# SL1_Xilinx_Spartan-IIE_PQ208_Rev1_01.net
KiCad netlist of a schematic drawn in Altium Designer
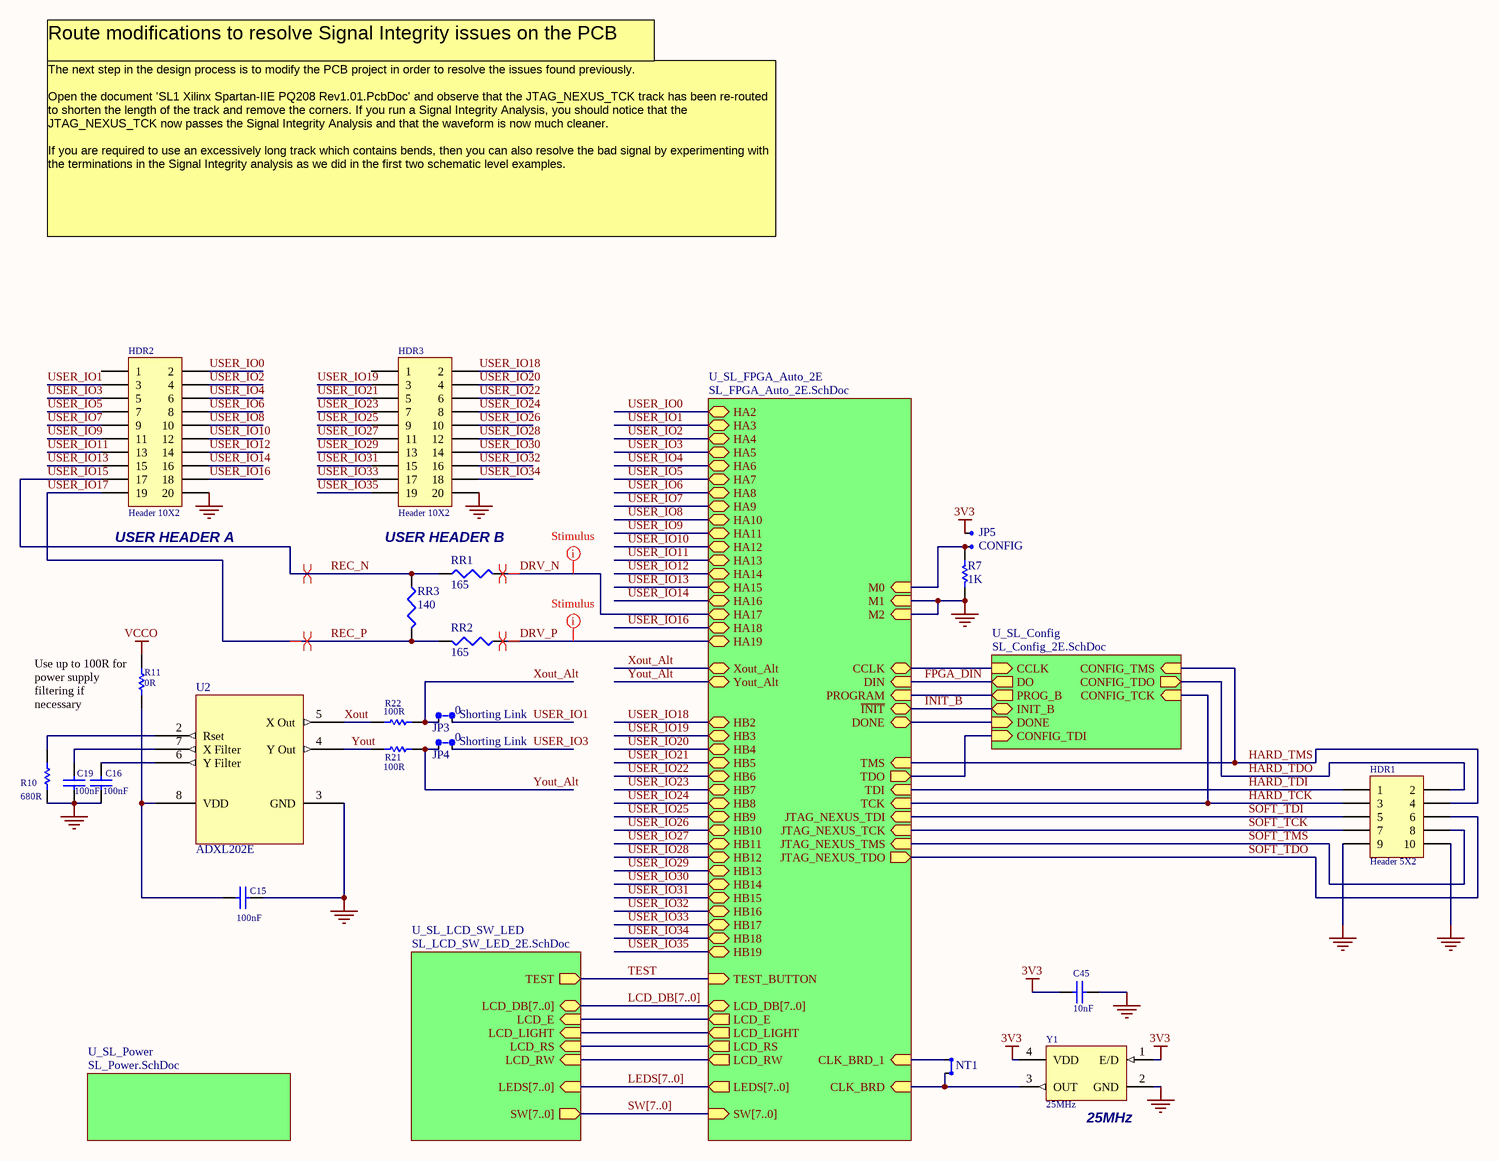
[diagram p0: SL1 Xilinx Spartan-IIE PQ208 Rev1.01.SchDoc]

(export (version "E")
  (design (tool "Eeschema 10.0.6"))
  (components
    (comp (ref "C15")
      (value "100nF")
      (footprint "CC1608-0603")
      (description "Capacitor")
      (libsource (lib "Test1") (part "CAP"))
    )
    (comp (ref "C16")
      (value "100nF")
      (footprint "CC1608-0603")
      (description "Capacitor")
      (libsource (lib "Test1") (part "CAP"))
    )
    (comp (ref "C19")
      (value "100nF")
      (footprint "CC1608-0603")
      (description "Capacitor")
      (libsource (lib "Test1") (part "CAP"))
    )
    (comp (ref "C45")
      (value "10nF")
      (footprint "CC1608-0603")
      (description "Capacitor")
      (libsource (lib "Test1") (part "CAP"))
    )
    (comp (ref "HDR1")
      (value "Header 5X2")
      (footprint "HDR2X5_LP")
      (description "Header, 5-Pin, Dual row")
      (libsource (lib "Miscellaneous Connectors") (part "Header 5X2"))
    )
    (comp (ref "HDR2")
      (value "Header 10X2")
      (footprint "Altium Nanoboard Project:HDR2X10")
      (description "Header, 10-Pin, Dual row")
      (libsource (lib "Altium Nanoboard Project") (part "Header 10X2"))
    )
    (comp (ref "HDR3")
      (value "Header 10X2")
      (footprint "Altium Nanoboard Project:HDR2X10")
      (description "Header, 10-Pin, Dual row")
      (libsource (lib "Altium Nanoboard Project") (part "Header 10X2"))
    )
    (comp (ref "JP3")
      (value "X axis")
      (footprint "Altium Nanoboard Project:HDR1X2")
      (description "Jumper, 2-Pin")
      (libsource (lib "SpiritLevel_2E") (part "Jumper, 2-Pin"))
    )
    (comp (ref "JP4")
      (value "Y axis")
      (footprint "Altium Nanoboard Project:HDR1X2")
      (description "Jumper, 2-Pin")
      (libsource (lib "SpiritLevel_2E") (part "Jumper, 2-Pin"))
    )
    (comp (ref "JP5")
      (value "CONFIG")
      (footprint "Altium Nanoboard Project:HDR1X2")
      (description "Jumper, 2-Pin")
      (libsource (lib "SpiritLevel_2E") (part "Jumper, 2-Pin"))
    )
    (comp (ref "JS2")
      (value "Shorting Link")
      (description "Shorting Link, 2.54mm (0.1\") Pitch")
      (fields (field (name "ALTIUM_VALUE") "0"))
      (libsource (lib "SpiritLevel_2E") (part "Jumper Socket"))
    )
    (comp (ref "JS3")
      (value "Shorting Link")
      (description "Shorting Link, 2.54mm (0.1\") Pitch")
      (fields (field (name "ALTIUM_VALUE") "0"))
      (libsource (lib "SpiritLevel_2E") (part "Jumper Socket"))
    )
    (comp (ref "NT1")
      (value "*")
      (footprint "NT")
      (description "Jumper, 2-Pin")
      (libsource (lib "SpiritLevel_2E") (part "Jumper, 2-Pin"))
    )
    (comp (ref "R7")
      (value "1K")
      (footprint "CR2012-0805")
      (description "Resistor")
      (libsource (lib "Altium Nanoboard Project") (part "RES"))
    )
    (comp (ref "R10")
      (value "680R")
      (footprint "CR2012-0805")
      (description "Resistor")
      (libsource (lib "Miscellaneous Devices") (part "Res1"))
    )
    (comp (ref "R11")
      (value "0R")
      (footprint "CR2012-0805")
      (description "Resistor")
      (libsource (lib "PassiveSMD") (part "RES"))
    )
    (comp (ref "R21")
      (value "100R")
      (footprint "CR2012-0805")
      (description "Resistor")
      (libsource (lib "Miscellaneous Devices") (part "Res1"))
    )
    (comp (ref "R22")
      (value "100R")
      (footprint "CR2012-0805")
      (description "Resistor")
      (libsource (lib "Miscellaneous Devices") (part "Res1"))
    )
    (comp (ref "RR1")
      (value "165")
      (footprint "J1-0603")
      (description "Resistor")
      (fields (field (name "Comment") "Res3") (field (name "PUBLISHER") "Altium Limited"))
      (libsource (lib "Miscellaneous Devices") (part "Res3"))
    )
    (comp (ref "RR2")
      (value "165")
      (footprint "J1-0603")
      (description "Resistor")
      (fields (field (name "Comment") "Res3") (field (name "PUBLISHER") "Altium Limited"))
      (libsource (lib "Miscellaneous Devices") (part "Res3"))
    )
    (comp (ref "RR3")
      (value "140")
      (footprint "J1-0603")
      (description "Resistor")
      (fields (field (name "Comment") "Res3") (field (name "PUBLISHER") "Altium Limited"))
      (libsource (lib "Miscellaneous Devices") (part "Res3"))
    )
    (comp (ref "U2")
      (value "ADXL202E")
      (footprint "Spirit_Level_Project:E-8")
      (description "Accelerometer with Digital Output")
      (libsource (lib "SpiritLevel_2E") (part "ADXL202E"))
    )
    (comp (ref "Y1")
      (value "25MHz")
      (footprint "Altium Nanoboard Project:QSMO_4200")
      (description "Surface Mount Crystal Oscillator")
      (libsource (lib "Altium Nanoboard Project") (part "QSMO_4200"))
    )
  )
  (nets
    (net (code "26") (name "/CLK_BRD") (class "Default")
      (node (ref "NT1") (pin "2") (pinfunction "2_2") (pintype "passive"))
      (node (ref "Y1") (pin "3") (pinfunction "OUT_3") (pintype "output"))
    )
    (net (code "27") (name "/CLK_BRD_1") (class "Default")
      (node (ref "NT1") (pin "1") (pinfunction "1_1") (pintype "passive"))
    )
    (net (code "29") (name "/DRV_N") (class "Default")
      (node (ref "RR1") (pin "1") (pinfunction "1_1") (pintype "passive"))
    )
    (net (code "30") (name "/DRV_P") (class "Default")
      (node (ref "RR2") (pin "2") (pinfunction "2_2") (pintype "passive"))
    )
    (net (code "32") (name "/HARD_TCK") (class "Default")
      (node (ref "HDR1") (pin "3") (pinfunction "3_3") (pintype "passive"))
    )
    (net (code "33") (name "/HARD_TDI") (class "Default")
      (node (ref "HDR1") (pin "1") (pinfunction "1_1") (pintype "passive"))
    )
    (net (code "34") (name "/HARD_TDO") (class "Default")
      (node (ref "HDR1") (pin "2") (pinfunction "2_2") (pintype "passive"))
    )
    (net (code "35") (name "/HARD_TMS") (class "Default")
      (node (ref "HDR1") (pin "4") (pinfunction "4_4") (pintype "passive"))
    )
    (net (code "43") (name "/M0") (class "Default")
      (node (ref "JP5") (pin "1") (pinfunction "1_1") (pintype "passive"))
      (node (ref "R7") (pin "2") (pinfunction "2_2") (pintype "passive"))
    )
    (net (code "45") (name "/REC_N") (class "Default")
      (node (ref "HDR2") (pin "17") (pinfunction "17_17") (pintype "passive"))
      (node (ref "RR1") (pin "2") (pinfunction "2_2") (pintype "passive"))
      (node (ref "RR3") (pin "2") (pinfunction "2_2") (pintype "passive"))
    )
    (net (code "46") (name "/REC_P") (class "Default")
      (node (ref "HDR2") (pin "19") (pinfunction "19_19") (pintype "passive"))
      (node (ref "RR2") (pin "1") (pinfunction "1_1") (pintype "passive"))
      (node (ref "RR3") (pin "1") (pinfunction "1_1") (pintype "passive"))
    )
    (net (code "47") (name "/SOFT_TCK") (class "Default")
      (node (ref "HDR1") (pin "7") (pinfunction "7_7") (pintype "passive"))
    )
    (net (code "48") (name "/SOFT_TDI") (class "Default")
      (node (ref "HDR1") (pin "5") (pinfunction "5_5") (pintype "passive"))
    )
    (net (code "49") (name "/SOFT_TDO") (class "Default")
      (node (ref "HDR1") (pin "6") (pinfunction "6_6") (pintype "passive"))
    )
    (net (code "50") (name "/SOFT_TMS") (class "Default")
      (node (ref "HDR1") (pin "8") (pinfunction "8_8") (pintype "passive"))
    )
    (net (code "54") (name "/USER_IO0") (class "Default")
      (node (ref "HDR2") (pin "2") (pinfunction "2_2") (pintype "passive"))
    )
    (net (code "55") (name "/USER_IO1") (class "Default")
      (node (ref "HDR2") (pin "3") (pinfunction "3_3") (pintype "passive"))
      (node (ref "JP3") (pin "2") (pinfunction "2_2") (pintype "passive"))
    )
    (net (code "56") (name "/USER_IO2") (class "Default")
      (node (ref "HDR2") (pin "4") (pinfunction "4_4") (pintype "passive"))
    )
    (net (code "57") (name "/USER_IO3") (class "Default")
      (node (ref "HDR2") (pin "5") (pinfunction "5_5") (pintype "passive"))
      (node (ref "JP4") (pin "2") (pinfunction "2_2") (pintype "passive"))
    )
    (net (code "58") (name "/USER_IO4") (class "Default")
      (node (ref "HDR2") (pin "6") (pinfunction "6_6") (pintype "passive"))
    )
    (net (code "59") (name "/USER_IO5") (class "Default")
      (node (ref "HDR2") (pin "7") (pinfunction "7_7") (pintype "passive"))
    )
    (net (code "60") (name "/USER_IO6") (class "Default")
      (node (ref "HDR2") (pin "8") (pinfunction "8_8") (pintype "passive"))
    )
    (net (code "61") (name "/USER_IO7") (class "Default")
      (node (ref "HDR2") (pin "9") (pinfunction "9_9") (pintype "passive"))
    )
    (net (code "62") (name "/USER_IO8") (class "Default")
      (node (ref "HDR2") (pin "10") (pinfunction "10_10") (pintype "passive"))
    )
    (net (code "63") (name "/USER_IO9") (class "Default")
      (node (ref "HDR2") (pin "11") (pinfunction "11_11") (pintype "passive"))
    )
    (net (code "64") (name "/USER_IO10") (class "Default")
      (node (ref "HDR2") (pin "12") (pinfunction "12_12") (pintype "passive"))
    )
    (net (code "65") (name "/USER_IO11") (class "Default")
      (node (ref "HDR2") (pin "13") (pinfunction "13_13") (pintype "passive"))
    )
    (net (code "66") (name "/USER_IO12") (class "Default")
      (node (ref "HDR2") (pin "14") (pinfunction "14_14") (pintype "passive"))
    )
    (net (code "67") (name "/USER_IO13") (class "Default")
      (node (ref "HDR2") (pin "15") (pinfunction "15_15") (pintype "passive"))
    )
    (net (code "68") (name "/USER_IO14") (class "Default")
      (node (ref "HDR2") (pin "16") (pinfunction "16_16") (pintype "passive"))
    )
    (net (code "69") (name "/USER_IO16") (class "Default")
      (node (ref "HDR2") (pin "18") (pinfunction "18_18") (pintype "passive"))
    )
    (net (code "70") (name "/USER_IO18") (class "Default")
      (node (ref "HDR3") (pin "2") (pinfunction "2_2") (pintype "passive"))
    )
    (net (code "71") (name "/USER_IO19") (class "Default")
      (node (ref "HDR3") (pin "3") (pinfunction "3_3") (pintype "passive"))
    )
    (net (code "72") (name "/USER_IO20") (class "Default")
      (node (ref "HDR3") (pin "4") (pinfunction "4_4") (pintype "passive"))
    )
    (net (code "73") (name "/USER_IO21") (class "Default")
      (node (ref "HDR3") (pin "5") (pinfunction "5_5") (pintype "passive"))
    )
    (net (code "74") (name "/USER_IO22") (class "Default")
      (node (ref "HDR3") (pin "6") (pinfunction "6_6") (pintype "passive"))
    )
    (net (code "75") (name "/USER_IO23") (class "Default")
      (node (ref "HDR3") (pin "7") (pinfunction "7_7") (pintype "passive"))
    )
    (net (code "76") (name "/USER_IO24") (class "Default")
      (node (ref "HDR3") (pin "8") (pinfunction "8_8") (pintype "passive"))
    )
    (net (code "77") (name "/USER_IO25") (class "Default")
      (node (ref "HDR3") (pin "9") (pinfunction "9_9") (pintype "passive"))
    )
    (net (code "78") (name "/USER_IO26") (class "Default")
      (node (ref "HDR3") (pin "10") (pinfunction "10_10") (pintype "passive"))
    )
    (net (code "79") (name "/USER_IO27") (class "Default")
      (node (ref "HDR3") (pin "11") (pinfunction "11_11") (pintype "passive"))
    )
    (net (code "80") (name "/USER_IO28") (class "Default")
      (node (ref "HDR3") (pin "12") (pinfunction "12_12") (pintype "passive"))
    )
    (net (code "81") (name "/USER_IO29") (class "Default")
      (node (ref "HDR3") (pin "13") (pinfunction "13_13") (pintype "passive"))
    )
    (net (code "82") (name "/USER_IO30") (class "Default")
      (node (ref "HDR3") (pin "14") (pinfunction "14_14") (pintype "passive"))
    )
    (net (code "83") (name "/USER_IO31") (class "Default")
      (node (ref "HDR3") (pin "15") (pinfunction "15_15") (pintype "passive"))
    )
    (net (code "84") (name "/USER_IO32") (class "Default")
      (node (ref "HDR3") (pin "16") (pinfunction "16_16") (pintype "passive"))
    )
    (net (code "85") (name "/USER_IO33") (class "Default")
      (node (ref "HDR3") (pin "17") (pinfunction "17_17") (pintype "passive"))
    )
    (net (code "86") (name "/USER_IO34") (class "Default")
      (node (ref "HDR3") (pin "18") (pinfunction "18_18") (pintype "passive"))
    )
    (net (code "87") (name "/USER_IO35") (class "Default")
      (node (ref "HDR3") (pin "19") (pinfunction "19_19") (pintype "passive"))
    )
    (net (code "88") (name "/Xout") (class "Default")
      (node (ref "R22") (pin "2") (pinfunction "2_2") (pintype "passive"))
      (node (ref "U2") (pin "5") (pinfunction "X_Out_5") (pintype "output"))
    )
    (net (code "89") (name "/Xout_Alt") (class "Default")
      (node (ref "JP3") (pin "1") (pinfunction "1_1") (pintype "passive"))
      (node (ref "R22") (pin "1") (pinfunction "1_1") (pintype "passive"))
    )
    (net (code "90") (name "/Yout") (class "Default")
      (node (ref "R21") (pin "2") (pinfunction "2_2") (pintype "passive"))
      (node (ref "U2") (pin "4") (pinfunction "Y_Out_4") (pintype "output"))
    )
    (net (code "91") (name "/Yout_Alt") (class "Default")
      (node (ref "JP4") (pin "1") (pinfunction "1_1") (pintype "passive"))
      (node (ref "R21") (pin "1") (pinfunction "1_1") (pintype "passive"))
    )
    (net (code "92") (name "3V3") (class "Default")
      (node (ref "C45") (pin "1") (pinfunction "1_1") (pintype "passive"))
      (node (ref "JP5") (pin "2") (pinfunction "2_2") (pintype "passive"))
      (node (ref "Y1") (pin "1") (pinfunction "E/D_1") (pintype "input"))
      (node (ref "Y1") (pin "4") (pinfunction "VDD_4") (pintype "power_in"))
    )
    (net (code "93") (name "GND") (class "Default")
      (node (ref "C15") (pin "2") (pinfunction "2_2") (pintype "passive"))
      (node (ref "C16") (pin "2") (pinfunction "2_2") (pintype "passive"))
      (node (ref "C19") (pin "2") (pinfunction "2_2") (pintype "passive"))
      (node (ref "C45") (pin "2") (pinfunction "2_2") (pintype "passive"))
      (node (ref "HDR1") (pin "10") (pinfunction "10_10") (pintype "passive"))
      (node (ref "HDR1") (pin "9") (pinfunction "9_9") (pintype "passive"))
      (node (ref "HDR2") (pin "20") (pinfunction "20_20") (pintype "passive"))
      (node (ref "HDR3") (pin "20") (pinfunction "20_20") (pintype "passive"))
      (node (ref "R10") (pin "1") (pinfunction "1_1") (pintype "passive"))
      (node (ref "R7") (pin "1") (pinfunction "1_1") (pintype "passive"))
      (node (ref "U2") (pin "3") (pinfunction "GND_3") (pintype "power_in"))
      (node (ref "Y1") (pin "2") (pinfunction "GND_2") (pintype "power_in"))
    )
    (net (code "94") (name "Net-(U2-Rset)") (class "Default")
      (node (ref "R10") (pin "2") (pinfunction "2_2") (pintype "passive"))
      (node (ref "U2") (pin "2") (pinfunction "Rset_2") (pintype "output"))
    )
    (net (code "95") (name "Net-(U2-VDD)") (class "Default")
      (node (ref "C15") (pin "1") (pinfunction "1_1") (pintype "passive"))
      (node (ref "R11") (pin "2") (pinfunction "2_2") (pintype "passive"))
      (node (ref "U2") (pin "8") (pinfunction "VDD_8") (pintype "power_in"))
    )
    (net (code "96") (name "Net-(U2-X_Filter)") (class "Default")
      (node (ref "C19") (pin "1") (pinfunction "1_1") (pintype "passive"))
      (node (ref "U2") (pin "7") (pinfunction "X_Filter_7") (pintype "output"))
    )
    (net (code "97") (name "Net-(U2-Y_Filter)") (class "Default")
      (node (ref "C16") (pin "1") (pinfunction "1_1") (pintype "passive"))
      (node (ref "U2") (pin "6") (pinfunction "Y_Filter_6") (pintype "output"))
    )
    (net (code "98") (name "VCCO") (class "Default")
      (node (ref "R11") (pin "1") (pinfunction "1_1") (pintype "passive"))
    )
    (net (code "99") (name "unconnected-(HDR2-Pad1)") (class "Default")
      (node (ref "HDR2") (pin "1") (pinfunction "1_1") (pintype "passive"))
    )
    (net (code "100") (name "unconnected-(HDR3-Pad1)") (class "Default")
      (node (ref "HDR3") (pin "1") (pinfunction "1_1") (pintype "passive"))
    )
    (net (code "101") (name "unconnected-(U2-Self_Test-Pad1)") (class "Default")
      (node (ref "U2") (pin "1") (pinfunction "Self_Test_1") (pintype "input"))
    )
  )
)
